# 04_GAP_GPIO.net
KiCad netlist of a schematic drawn in Altium Designer
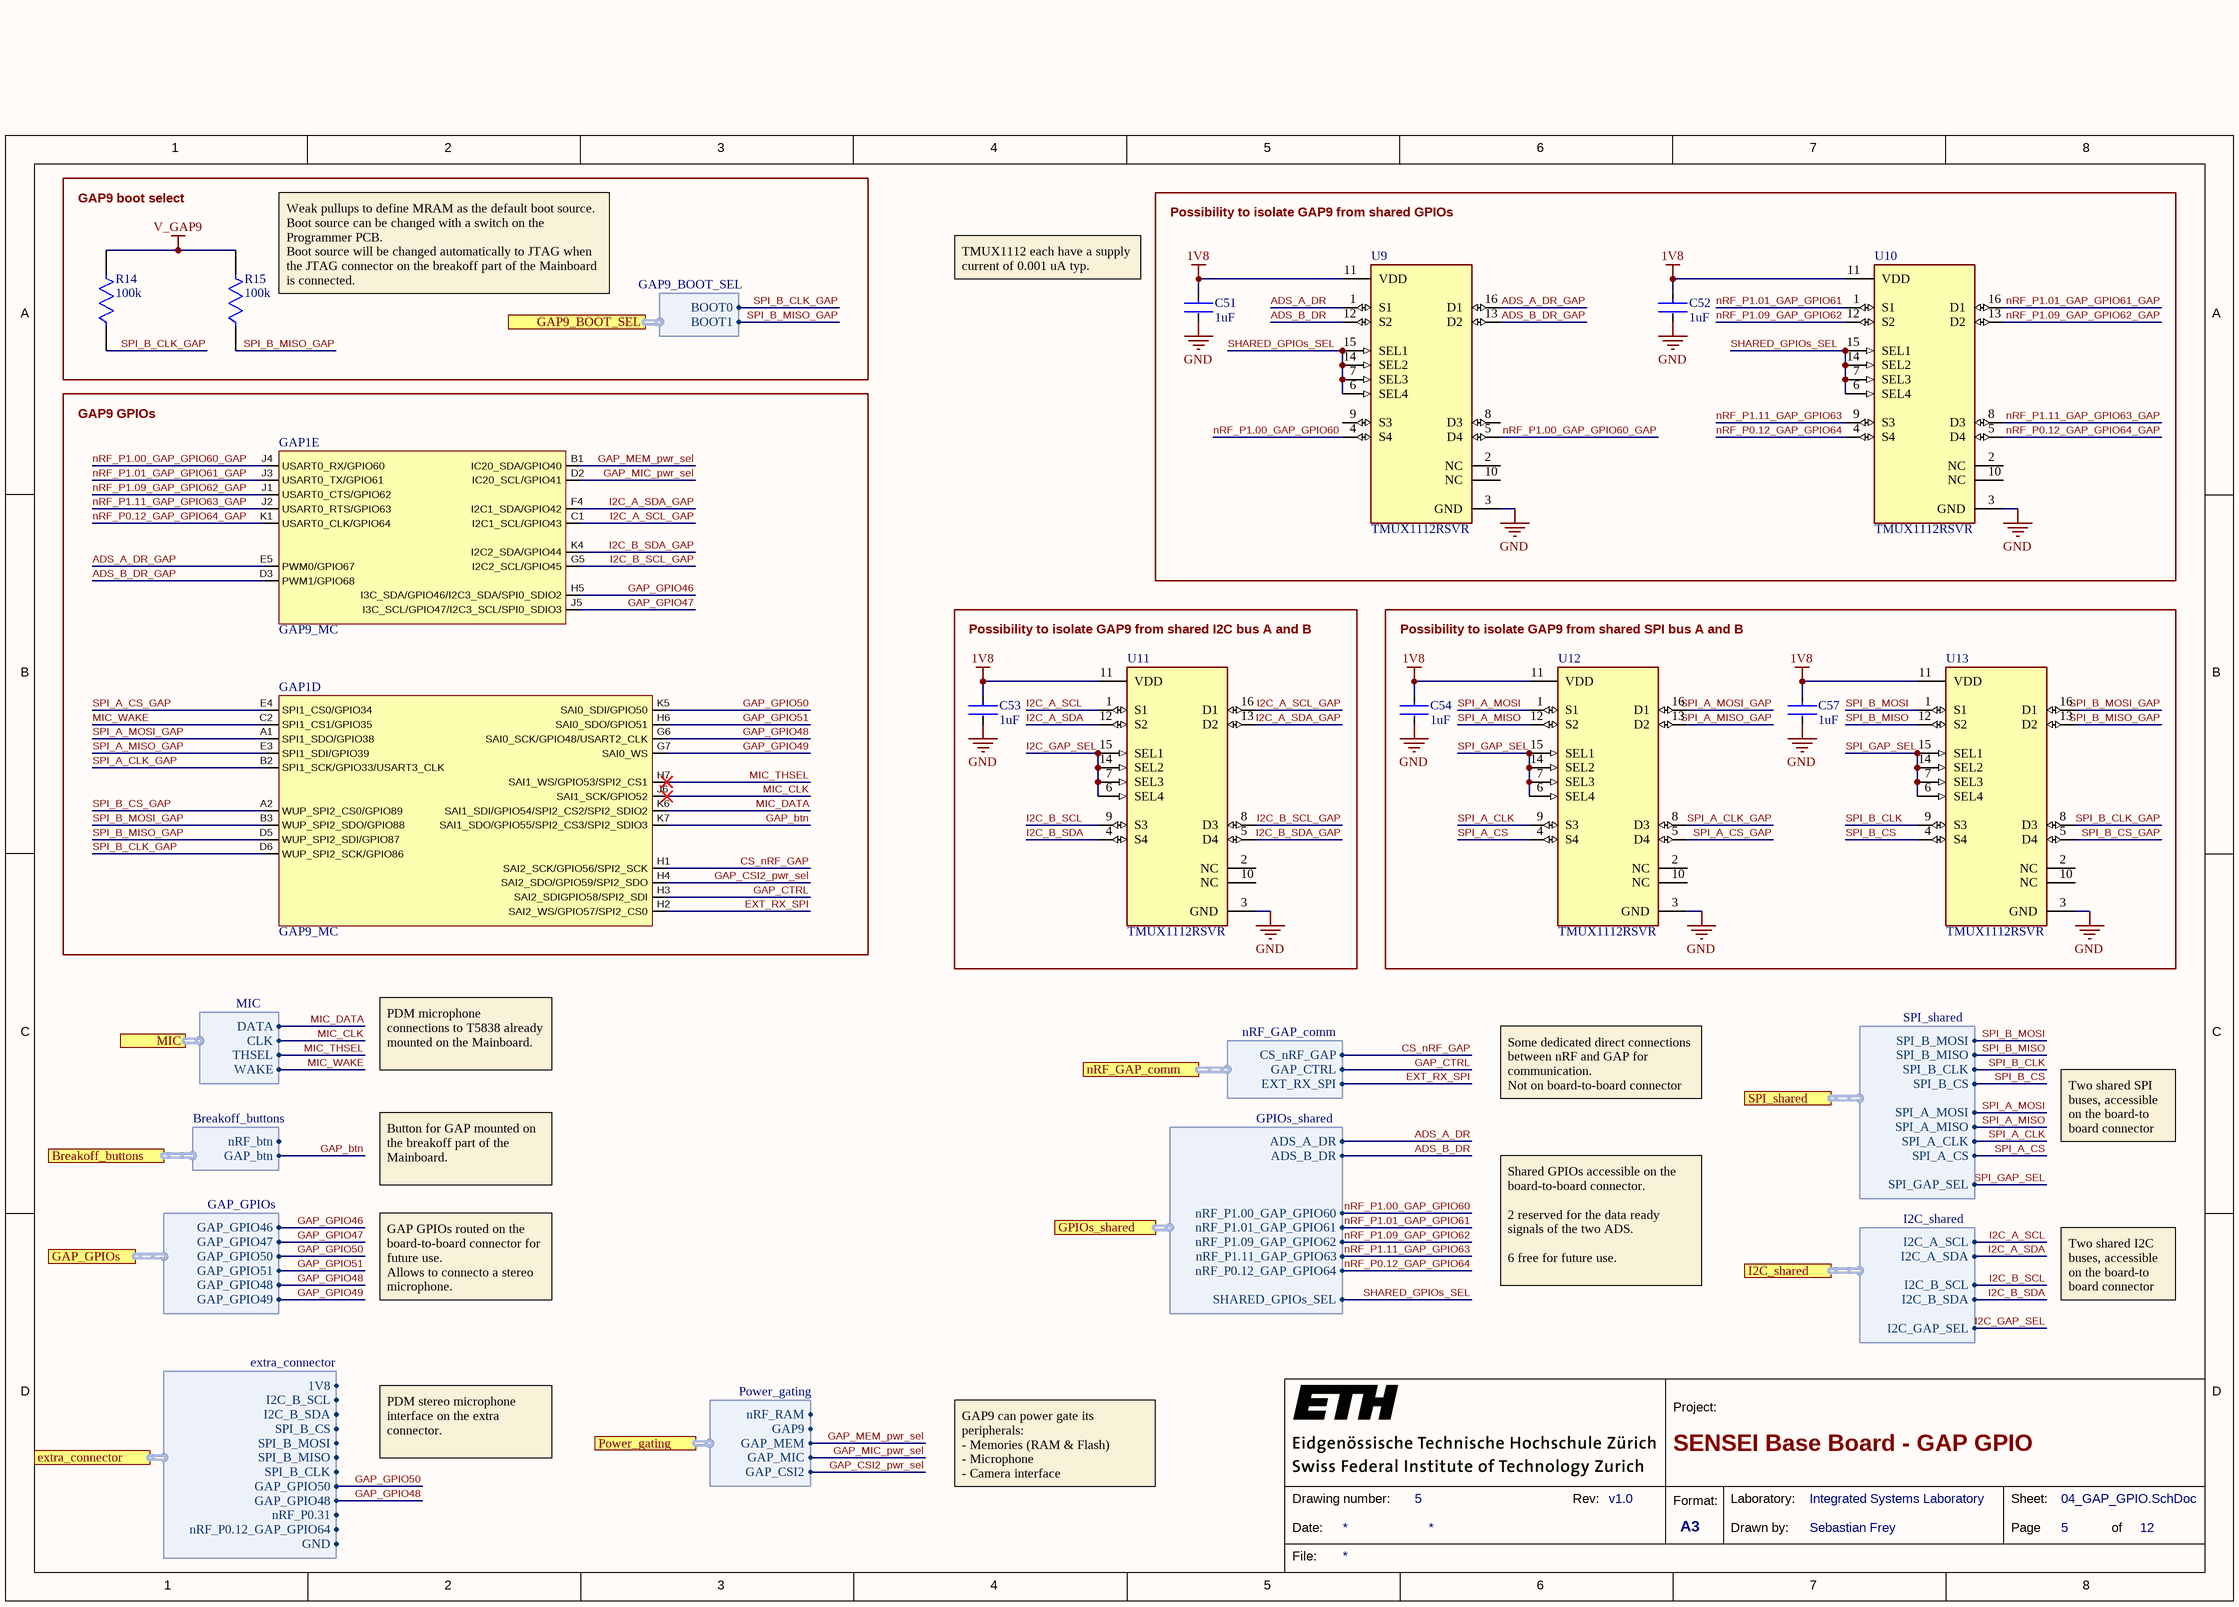
[diagram p0: 04_GAP_GPIO.SchDoc]

(export (version "E")
  (design (tool "Eeschema 10.0.6"))
  (components
    (comp (ref "C51")
      (value "CL03A105KP3NSNC")
      (footprint "FP-CL03-IPC_B")
      (description "Cap Ceramic 1uF 10V X5R ±10% Pad SMD 0201 +85°C T/R")
      (fields (field (name "TOLERANCE") "10%") (field (name "CAPACITANCE") "1uF"))
      (libsource (lib "Altium Content Vault") (part "b4654b650e69147ec39a6b967a45e02"))
    )
    (comp (ref "C52")
      (value "CL03A105KP3NSNC")
      (footprint "FP-CL03-IPC_B")
      (description "Cap Ceramic 1uF 10V X5R ±10% Pad SMD 0201 +85°C T/R")
      (fields (field (name "TOLERANCE") "10%") (field (name "CAPACITANCE") "1uF"))
      (libsource (lib "Altium Content Vault") (part "b4654b650e69147ec39a6b967a45e02"))
    )
    (comp (ref "C53")
      (value "CL03A105KP3NSNC")
      (footprint "FP-CL03-IPC_B")
      (description "Cap Ceramic 1uF 10V X5R ±10% Pad SMD 0201 +85°C T/R")
      (fields (field (name "TOLERANCE") "10%") (field (name "CAPACITANCE") "1uF"))
      (libsource (lib "Altium Content Vault") (part "b4654b650e69147ec39a6b967a45e02"))
    )
    (comp (ref "C54")
      (value "CL03A105KP3NSNC")
      (footprint "FP-CL03-IPC_B")
      (description "Cap Ceramic 1uF 10V X5R ±10% Pad SMD 0201 +85°C T/R")
      (fields (field (name "TOLERANCE") "10%") (field (name "CAPACITANCE") "1uF"))
      (libsource (lib "Altium Content Vault") (part "b4654b650e69147ec39a6b967a45e02"))
    )
    (comp (ref "C57")
      (value "CL03A105KP3NSNC")
      (footprint "FP-CL03-IPC_B")
      (description "Cap Ceramic 1uF 10V X5R ±10% Pad SMD 0201 +85°C T/R")
      (fields (field (name "TOLERANCE") "10%") (field (name "CAPACITANCE") "1uF"))
      (libsource (lib "Altium Content Vault") (part "b4654b650e69147ec39a6b967a45e02"))
    )
    (comp (ref "GAP1")
      (value "GAP9_MC")
      (footprint "EEG_PcbLib:GAP9")
      (libsource (lib "EEG_SchLib") (part "GAP9_MC"))
    )
    (comp (ref "R14")
      (value "RR0510P-104-D")
      (footprint "FP-RR0510-IPC_C")
      (description "100kΩ ±0.5% 0.0625W 1/16W Chip Resistor 0402 (1005 Metric) Thin Film")
      (fields (field (name "RESISTANCE") "100k") (field (name "TOLERANCE") "0.5%"))
      (libsource (lib "Altium Content Vault") (part "1029c3af85768c4190bb7ad29bc67b5"))
    )
    (comp (ref "R15")
      (value "RR0510P-104-D")
      (footprint "FP-RR0510-IPC_C")
      (description "100kΩ ±0.5% 0.0625W 1/16W Chip Resistor 0402 (1005 Metric) Thin Film")
      (fields (field (name "RESISTANCE") "100k") (field (name "TOLERANCE") "0.5%"))
      (libsource (lib "Altium Content Vault") (part "1029c3af85768c4190bb7ad29bc67b5"))
    )
    (comp (ref "U9")
      (value "TMUX1112RSVR")
      (footprint "FP-RSV0016A-MFG")
      (description "IC SWITCH")
      (fields
        (field (name "MANUFACTURER") "Texas Instruments")
        (field (name "OCTOPART") "https://octopart.com/tmux1112rsvr-texas+instruments-99389231")
      )
      (libsource (lib "Altium Content Vault") (part "3b04d19269abb49724e69affa1d4afe"))
    )
    (comp (ref "U10")
      (value "TMUX1112RSVR")
      (footprint "FP-RSV0016A-MFG")
      (description "IC SWITCH")
      (fields
        (field (name "MANUFACTURER") "Texas Instruments")
        (field (name "OCTOPART") "https://octopart.com/tmux1112rsvr-texas+instruments-99389231")
      )
      (libsource (lib "Altium Content Vault") (part "3b04d19269abb49724e69affa1d4afe"))
    )
    (comp (ref "U11")
      (value "TMUX1112RSVR")
      (footprint "FP-RSV0016A-MFG")
      (description "IC SWITCH")
      (fields
        (field (name "MANUFACTURER") "Texas Instruments")
        (field (name "OCTOPART") "https://octopart.com/tmux1112rsvr-texas+instruments-99389231")
      )
      (libsource (lib "Altium Content Vault") (part "3b04d19269abb49724e69affa1d4afe"))
    )
    (comp (ref "U12")
      (value "TMUX1112RSVR")
      (footprint "FP-RSV0016A-MFG")
      (description "IC SWITCH")
      (fields
        (field (name "MANUFACTURER") "Texas Instruments")
        (field (name "OCTOPART") "https://octopart.com/tmux1112rsvr-texas+instruments-99389231")
      )
      (libsource (lib "Altium Content Vault") (part "3b04d19269abb49724e69affa1d4afe"))
    )
    (comp (ref "U13")
      (value "TMUX1112RSVR")
      (footprint "FP-RSV0016A-MFG")
      (description "IC SWITCH")
      (fields
        (field (name "MANUFACTURER") "Texas Instruments")
        (field (name "OCTOPART") "https://octopart.com/tmux1112rsvr-texas+instruments-99389231")
      )
      (libsource (lib "Altium Content Vault") (part "3b04d19269abb49724e69affa1d4afe"))
    )
  )
  (nets
    (net (code "11") (name "/ADS_A_DR") (class "Default")
      (node (ref "U9") (pin "1") (pinfunction "S1_1") (pintype "bidirectional"))
    )
    (net (code "12") (name "/ADS_A_DR_GAP") (class "Default")
      (node (ref "GAP1") (pin "E5") (pinfunction "PWM0/GPIO67_E5") (pintype "passive"))
      (node (ref "U9") (pin "16") (pinfunction "D1_16") (pintype "bidirectional"))
    )
    (net (code "13") (name "/ADS_B_DR") (class "Default")
      (node (ref "U9") (pin "12") (pinfunction "S2_12") (pintype "bidirectional"))
    )
    (net (code "14") (name "/ADS_B_DR_GAP") (class "Default")
      (node (ref "GAP1") (pin "D3") (pinfunction "PWM1/GPIO68_D3") (pintype "passive"))
      (node (ref "U9") (pin "13") (pinfunction "D2_13") (pintype "bidirectional"))
    )
    (net (code "15") (name "/CS_nRF_GAP") (class "Default")
      (node (ref "GAP1") (pin "H1") (pinfunction "SAI2_SCK/GPIO56/SPI2_SCK_H1") (pintype "passive"))
    )
    (net (code "16") (name "/EXT_RX_SPI") (class "Default")
      (node (ref "GAP1") (pin "H2") (pinfunction "SAI2_WS/GPIO57/SPI2_CS0_H2") (pintype "passive"))
    )
    (net (code "17") (name "/GAP_CSI2_pwr_sel") (class "Default")
      (node (ref "GAP1") (pin "H4") (pinfunction "SAI2_SDO/GPIO59/SPI2_SDO_H4") (pintype "passive"))
    )
    (net (code "18") (name "/GAP_CTRL") (class "Default")
      (node (ref "GAP1") (pin "H3") (pinfunction "SAI2_SDIGPIO58/SPI2_SDI_H3") (pintype "passive"))
    )
    (net (code "19") (name "/GAP_GPIO46") (class "Default")
      (node (ref "GAP1") (pin "H5") (pinfunction "I3C_SDA/GPIO46/I2C3_SDA/SPI0_SDIO2_H5") (pintype "passive"))
    )
    (net (code "20") (name "/GAP_GPIO47") (class "Default")
      (node (ref "GAP1") (pin "J5") (pinfunction "I3C_SCL/GPIO47/I2C3_SCL/SPI0_SDIO3_J5") (pintype "passive"))
    )
    (net (code "21") (name "/GAP_GPIO48") (class "Default")
      (node (ref "GAP1") (pin "G6") (pinfunction "SAI0_SCK/GPIO48/USART2_CLK_G6") (pintype "passive"))
    )
    (net (code "22") (name "/GAP_GPIO49") (class "Default")
      (node (ref "GAP1") (pin "G7") (pinfunction "SAI0_WS_G7") (pintype "passive"))
    )
    (net (code "23") (name "/GAP_GPIO50") (class "Default")
      (node (ref "GAP1") (pin "K5") (pinfunction "SAI0_SDI/GPIO50_K5") (pintype "passive"))
    )
    (net (code "24") (name "/GAP_GPIO51") (class "Default")
      (node (ref "GAP1") (pin "H6") (pinfunction "SAI0_SDO/GPIO51_H6") (pintype "passive"))
    )
    (net (code "25") (name "/GAP_MEM_pwr_sel") (class "Default")
      (node (ref "GAP1") (pin "B1") (pinfunction "IC20_SDA/GPIO40_B1") (pintype "passive"))
    )
    (net (code "26") (name "/GAP_MIC_pwr_sel") (class "Default")
      (node (ref "GAP1") (pin "D2") (pinfunction "IC20_SCL/GPIO41_D2") (pintype "passive"))
    )
    (net (code "27") (name "/GAP_btn") (class "Default")
      (node (ref "GAP1") (pin "K7") (pinfunction "SAI1_SDO/GPIO55/SPI2_CS3/SPI2_SDIO3_K7") (pintype "passive"))
    )
    (net (code "28") (name "/I2C_A_SCL") (class "Default")
      (node (ref "U11") (pin "1") (pinfunction "S1_1") (pintype "bidirectional"))
    )
    (net (code "29") (name "/I2C_A_SCL_GAP") (class "Default")
      (node (ref "GAP1") (pin "C1") (pinfunction "I2C1_SCL/GPIO43_C1") (pintype "passive"))
      (node (ref "U11") (pin "16") (pinfunction "D1_16") (pintype "bidirectional"))
    )
    (net (code "30") (name "/I2C_A_SDA") (class "Default")
      (node (ref "U11") (pin "12") (pinfunction "S2_12") (pintype "bidirectional"))
    )
    (net (code "31") (name "/I2C_A_SDA_GAP") (class "Default")
      (node (ref "GAP1") (pin "F4") (pinfunction "I2C1_SDA/GPIO42_F4") (pintype "passive"))
      (node (ref "U11") (pin "13") (pinfunction "D2_13") (pintype "bidirectional"))
    )
    (net (code "32") (name "/I2C_B_SCL") (class "Default")
      (node (ref "U11") (pin "9") (pinfunction "S3_9") (pintype "bidirectional"))
    )
    (net (code "33") (name "/I2C_B_SCL_GAP") (class "Default")
      (node (ref "GAP1") (pin "G5") (pinfunction "I2C2_SCL/GPIO45_G5") (pintype "passive"))
      (node (ref "U11") (pin "8") (pinfunction "D3_8") (pintype "bidirectional"))
    )
    (net (code "34") (name "/I2C_B_SDA") (class "Default")
      (node (ref "U11") (pin "4") (pinfunction "S4_4") (pintype "bidirectional"))
    )
    (net (code "35") (name "/I2C_B_SDA_GAP") (class "Default")
      (node (ref "GAP1") (pin "K4") (pinfunction "I2C2_SDA/GPIO44_K4") (pintype "passive"))
      (node (ref "U11") (pin "5") (pinfunction "D4_5") (pintype "bidirectional"))
    )
    (net (code "36") (name "/I2C_GAP_SEL") (class "Default")
      (node (ref "U11") (pin "14") (pinfunction "SEL2_14") (pintype "input"))
      (node (ref "U11") (pin "15") (pinfunction "SEL1_15") (pintype "input"))
      (node (ref "U11") (pin "6") (pinfunction "SEL4_6") (pintype "input"))
      (node (ref "U11") (pin "7") (pinfunction "SEL3_7") (pintype "input"))
    )
    (net (code "37") (name "/MIC_CLK") (class "Default")
      (node (ref "GAP1") (pin "J6") (pinfunction "SAI1_SCK/GPIO52_J6") (pintype "passive+no_connect"))
    )
    (net (code "38") (name "/MIC_DATA") (class "Default")
      (node (ref "GAP1") (pin "K6") (pinfunction "SAI1_SDI/GPIO54/SPI2_CS2/SPI2_SDIO2_K6") (pintype "passive"))
    )
    (net (code "39") (name "/MIC_THSEL") (class "Default")
      (node (ref "GAP1") (pin "H7") (pinfunction "SAI1_WS/GPIO53/SPI2_CS1_H7") (pintype "passive+no_connect"))
    )
    (net (code "40") (name "/MIC_WAKE") (class "Default")
      (node (ref "GAP1") (pin "C2") (pinfunction "SPI1_CS1/GPIO35_C2") (pintype "passive"))
    )
    (net (code "41") (name "/SHARED_GPIOs_SEL") (class "Default")
      (node (ref "U10") (pin "14") (pinfunction "SEL2_14") (pintype "input"))
      (node (ref "U10") (pin "15") (pinfunction "SEL1_15") (pintype "input"))
      (node (ref "U10") (pin "6") (pinfunction "SEL4_6") (pintype "input"))
      (node (ref "U10") (pin "7") (pinfunction "SEL3_7") (pintype "input"))
      (node (ref "U9") (pin "14") (pinfunction "SEL2_14") (pintype "input"))
      (node (ref "U9") (pin "15") (pinfunction "SEL1_15") (pintype "input"))
      (node (ref "U9") (pin "6") (pinfunction "SEL4_6") (pintype "input"))
      (node (ref "U9") (pin "7") (pinfunction "SEL3_7") (pintype "input"))
    )
    (net (code "42") (name "/SPI_A_CLK") (class "Default")
      (node (ref "U12") (pin "9") (pinfunction "S3_9") (pintype "bidirectional"))
    )
    (net (code "43") (name "/SPI_A_CLK_GAP") (class "Default")
      (node (ref "GAP1") (pin "B2") (pinfunction "SPI1_SCK/GPIO33/USART3_CLK_B2") (pintype "passive"))
      (node (ref "U12") (pin "8") (pinfunction "D3_8") (pintype "bidirectional"))
    )
    (net (code "44") (name "/SPI_A_CS") (class "Default")
      (node (ref "U12") (pin "4") (pinfunction "S4_4") (pintype "bidirectional"))
    )
    (net (code "45") (name "/SPI_A_CS_GAP") (class "Default")
      (node (ref "GAP1") (pin "E4") (pinfunction "SPI1_CS0/GPIO34_E4") (pintype "passive"))
      (node (ref "U12") (pin "5") (pinfunction "D4_5") (pintype "bidirectional"))
    )
    (net (code "46") (name "/SPI_A_MISO") (class "Default")
      (node (ref "U12") (pin "12") (pinfunction "S2_12") (pintype "bidirectional"))
    )
    (net (code "47") (name "/SPI_A_MISO_GAP") (class "Default")
      (node (ref "GAP1") (pin "E3") (pinfunction "SPI1_SDI/GPIO39_E3") (pintype "passive"))
      (node (ref "U12") (pin "13") (pinfunction "D2_13") (pintype "bidirectional"))
    )
    (net (code "48") (name "/SPI_A_MOSI") (class "Default")
      (node (ref "U12") (pin "1") (pinfunction "S1_1") (pintype "bidirectional"))
    )
    (net (code "49") (name "/SPI_A_MOSI_GAP") (class "Default")
      (node (ref "GAP1") (pin "A1") (pinfunction "SPI1_SDO/GPIO38_A1") (pintype "passive"))
      (node (ref "U12") (pin "16") (pinfunction "D1_16") (pintype "bidirectional"))
    )
    (net (code "50") (name "/SPI_B_CLK") (class "Default")
      (node (ref "U13") (pin "9") (pinfunction "S3_9") (pintype "bidirectional"))
    )
    (net (code "51") (name "/SPI_B_CLK_GAP") (class "Default")
      (node (ref "GAP1") (pin "D6") (pinfunction "WUP_SPI2_SCK/GPIO86_D6") (pintype "passive"))
      (node (ref "R14") (pin "1") (pinfunction "1_1") (pintype "passive"))
      (node (ref "U13") (pin "8") (pinfunction "D3_8") (pintype "bidirectional"))
    )
    (net (code "52") (name "/SPI_B_CS") (class "Default")
      (node (ref "U13") (pin "4") (pinfunction "S4_4") (pintype "bidirectional"))
    )
    (net (code "53") (name "/SPI_B_CS_GAP") (class "Default")
      (node (ref "GAP1") (pin "A2") (pinfunction "WUP_SPI2_CS0/GPIO89_A2") (pintype "passive"))
      (node (ref "U13") (pin "5") (pinfunction "D4_5") (pintype "bidirectional"))
    )
    (net (code "54") (name "/SPI_B_MISO") (class "Default")
      (node (ref "U13") (pin "12") (pinfunction "S2_12") (pintype "bidirectional"))
    )
    (net (code "55") (name "/SPI_B_MISO_GAP") (class "Default")
      (node (ref "GAP1") (pin "D5") (pinfunction "WUP_SPI2_SDI/GPIO87_D5") (pintype "passive"))
      (node (ref "R15") (pin "1") (pinfunction "1_1") (pintype "passive"))
      (node (ref "U13") (pin "13") (pinfunction "D2_13") (pintype "bidirectional"))
    )
    (net (code "56") (name "/SPI_B_MOSI") (class "Default")
      (node (ref "U13") (pin "1") (pinfunction "S1_1") (pintype "bidirectional"))
    )
    (net (code "57") (name "/SPI_B_MOSI_GAP") (class "Default")
      (node (ref "GAP1") (pin "B3") (pinfunction "WUP_SPI2_SDO/GPIO88_B3") (pintype "passive"))
      (node (ref "U13") (pin "16") (pinfunction "D1_16") (pintype "bidirectional"))
    )
    (net (code "58") (name "/SPI_GAP_SEL") (class "Default")
      (node (ref "U12") (pin "14") (pinfunction "SEL2_14") (pintype "input"))
      (node (ref "U12") (pin "15") (pinfunction "SEL1_15") (pintype "input"))
      (node (ref "U12") (pin "6") (pinfunction "SEL4_6") (pintype "input"))
      (node (ref "U12") (pin "7") (pinfunction "SEL3_7") (pintype "input"))
      (node (ref "U13") (pin "14") (pinfunction "SEL2_14") (pintype "input"))
      (node (ref "U13") (pin "15") (pinfunction "SEL1_15") (pintype "input"))
      (node (ref "U13") (pin "6") (pinfunction "SEL4_6") (pintype "input"))
      (node (ref "U13") (pin "7") (pinfunction "SEL3_7") (pintype "input"))
    )
    (net (code "59") (name "/nRF_P0.12_GAP_GPIO64") (class "Default")
      (node (ref "U10") (pin "4") (pinfunction "S4_4") (pintype "bidirectional"))
    )
    (net (code "60") (name "/nRF_P0.12_GAP_GPIO64_GAP") (class "Default")
      (node (ref "GAP1") (pin "K1") (pinfunction "USART0_CLK/GPIO64_K1") (pintype "passive"))
      (node (ref "U10") (pin "5") (pinfunction "D4_5") (pintype "bidirectional"))
    )
    (net (code "61") (name "/nRF_P1.00_GAP_GPIO60") (class "Default")
      (node (ref "U9") (pin "4") (pinfunction "S4_4") (pintype "bidirectional"))
    )
    (net (code "62") (name "/nRF_P1.00_GAP_GPIO60_GAP") (class "Default")
      (node (ref "GAP1") (pin "J4") (pinfunction "USART0_RX/GPIO60_J4") (pintype "passive"))
      (node (ref "U9") (pin "5") (pinfunction "D4_5") (pintype "bidirectional"))
    )
    (net (code "63") (name "/nRF_P1.01_GAP_GPIO61") (class "Default")
      (node (ref "U10") (pin "1") (pinfunction "S1_1") (pintype "bidirectional"))
    )
    (net (code "64") (name "/nRF_P1.01_GAP_GPIO61_GAP") (class "Default")
      (node (ref "GAP1") (pin "J3") (pinfunction "USART0_TX/GPIO61_J3") (pintype "passive"))
      (node (ref "U10") (pin "16") (pinfunction "D1_16") (pintype "bidirectional"))
    )
    (net (code "65") (name "/nRF_P1.09_GAP_GPIO62") (class "Default")
      (node (ref "U10") (pin "12") (pinfunction "S2_12") (pintype "bidirectional"))
    )
    (net (code "66") (name "/nRF_P1.09_GAP_GPIO62_GAP") (class "Default")
      (node (ref "GAP1") (pin "J1") (pinfunction "USART0_CTS/GPIO62_J1") (pintype "passive"))
      (node (ref "U10") (pin "13") (pinfunction "D2_13") (pintype "bidirectional"))
    )
    (net (code "67") (name "/nRF_P1.11_GAP_GPIO63") (class "Default")
      (node (ref "U10") (pin "9") (pinfunction "S3_9") (pintype "bidirectional"))
    )
    (net (code "68") (name "/nRF_P1.11_GAP_GPIO63_GAP") (class "Default")
      (node (ref "GAP1") (pin "J2") (pinfunction "USART0_RTS/GPIO63_J2") (pintype "passive"))
      (node (ref "U10") (pin "8") (pinfunction "D3_8") (pintype "bidirectional"))
    )
    (net (code "79") (name "1V8") (class "Default")
      (node (ref "C51") (pin "1") (pinfunction "1_1") (pintype "passive"))
      (node (ref "C52") (pin "1") (pinfunction "1_1") (pintype "passive"))
      (node (ref "C53") (pin "1") (pinfunction "1_1") (pintype "passive"))
      (node (ref "C54") (pin "1") (pinfunction "1_1") (pintype "passive"))
      (node (ref "C57") (pin "1") (pinfunction "1_1") (pintype "passive"))
      (node (ref "U10") (pin "11") (pinfunction "VDD_11") (pintype "power_in"))
      (node (ref "U11") (pin "11") (pinfunction "VDD_11") (pintype "power_in"))
      (node (ref "U12") (pin "11") (pinfunction "VDD_11") (pintype "power_in"))
      (node (ref "U13") (pin "11") (pinfunction "VDD_11") (pintype "power_in"))
      (node (ref "U9") (pin "11") (pinfunction "VDD_11") (pintype "power_in"))
    )
    (net (code "80") (name "GND") (class "Default")
      (node (ref "C51") (pin "2") (pinfunction "2_2") (pintype "passive"))
      (node (ref "C52") (pin "2") (pinfunction "2_2") (pintype "passive"))
      (node (ref "C53") (pin "2") (pinfunction "2_2") (pintype "passive"))
      (node (ref "C54") (pin "2") (pinfunction "2_2") (pintype "passive"))
      (node (ref "C57") (pin "2") (pinfunction "2_2") (pintype "passive"))
      (node (ref "U10") (pin "3") (pinfunction "GND_3") (pintype "power_in"))
      (node (ref "U11") (pin "3") (pinfunction "GND_3") (pintype "power_in"))
      (node (ref "U12") (pin "3") (pinfunction "GND_3") (pintype "power_in"))
      (node (ref "U13") (pin "3") (pinfunction "GND_3") (pintype "power_in"))
      (node (ref "U9") (pin "3") (pinfunction "GND_3") (pintype "power_in"))
    )
    (net (code "81") (name "V_GAP9") (class "Default")
      (node (ref "R14") (pin "2") (pinfunction "2_2") (pintype "passive"))
      (node (ref "R15") (pin "2") (pinfunction "2_2") (pintype "passive"))
    )
    (net (code "82") (name "unconnected-(U9-D3-Pad8)") (class "Default")
      (node (ref "U9") (pin "8") (pinfunction "D3_8") (pintype "bidirectional"))
    )
    (net (code "83") (name "unconnected-(U9-NC-Pad2)") (class "Default")
      (node (ref "U9") (pin "2") (pinfunction "NC_2") (pintype "passive"))
    )
    (net (code "84") (name "unconnected-(U9-NC-Pad10)") (class "Default")
      (node (ref "U9") (pin "10") (pinfunction "NC_10") (pintype "passive"))
    )
    (net (code "85") (name "unconnected-(U9-S3-Pad9)") (class "Default")
      (node (ref "U9") (pin "9") (pinfunction "S3_9") (pintype "bidirectional"))
    )
    (net (code "86") (name "unconnected-(U10-NC-Pad2)") (class "Default")
      (node (ref "U10") (pin "2") (pinfunction "NC_2") (pintype "passive"))
    )
    (net (code "87") (name "unconnected-(U10-NC-Pad10)") (class "Default")
      (node (ref "U10") (pin "10") (pinfunction "NC_10") (pintype "passive"))
    )
    (net (code "88") (name "unconnected-(U11-NC-Pad2)") (class "Default")
      (node (ref "U11") (pin "2") (pinfunction "NC_2") (pintype "passive"))
    )
    (net (code "89") (name "unconnected-(U11-NC-Pad10)") (class "Default")
      (node (ref "U11") (pin "10") (pinfunction "NC_10") (pintype "passive"))
    )
    (net (code "90") (name "unconnected-(U12-NC-Pad2)") (class "Default")
      (node (ref "U12") (pin "2") (pinfunction "NC_2") (pintype "passive"))
    )
    (net (code "91") (name "unconnected-(U12-NC-Pad10)") (class "Default")
      (node (ref "U12") (pin "10") (pinfunction "NC_10") (pintype "passive"))
    )
    (net (code "92") (name "unconnected-(U13-NC-Pad2)") (class "Default")
      (node (ref "U13") (pin "2") (pinfunction "NC_2") (pintype "passive"))
    )
    (net (code "93") (name "unconnected-(U13-NC-Pad10)") (class "Default")
      (node (ref "U13") (pin "10") (pinfunction "NC_10") (pintype "passive"))
    )
  )
)
